# FPGA_OV7670.net
KiCad netlist of a schematic drawn in Altium Designer
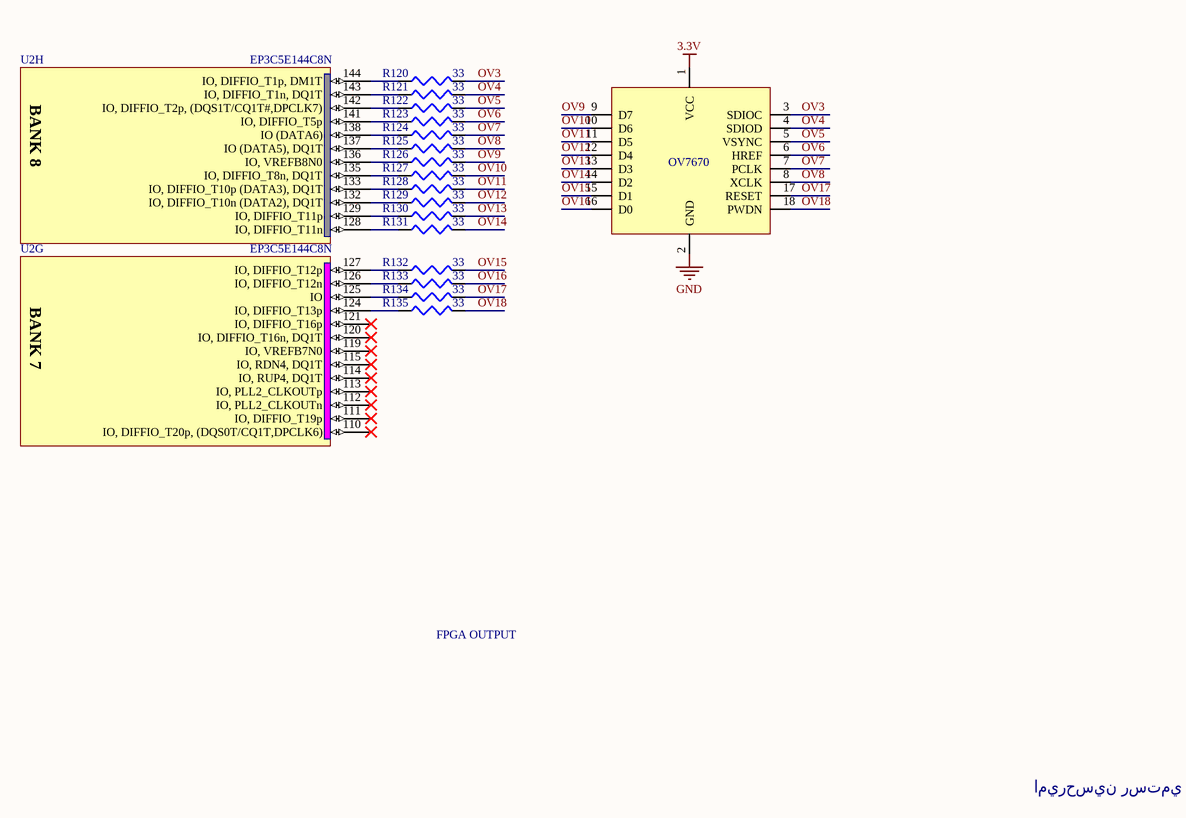
[diagram p0: FPGA_OV7670.SchDoc]

(export (version "E")
  (design (tool "Eeschema 10.0.6"))
  (components
    (comp (ref "*") (value "Component_1") (libsource (lib "OV7670") (part "Component_1")))
    (comp (ref "R120")
      (value "33")
      (footprint "J1-0603")
      (description "Resistor")
      (fields (field (name "PUBLISHER") "Altium Limited"))
      (libsource (lib "Miscellaneous Devices") (part "Res3"))
    )
    (comp (ref "R121")
      (value "33")
      (footprint "J1-0603")
      (description "Resistor")
      (fields (field (name "PUBLISHER") "Altium Limited"))
      (libsource (lib "Miscellaneous Devices") (part "Res3"))
    )
    (comp (ref "R122")
      (value "33")
      (footprint "J1-0603")
      (description "Resistor")
      (fields (field (name "PUBLISHER") "Altium Limited"))
      (libsource (lib "Miscellaneous Devices") (part "Res3"))
    )
    (comp (ref "R123")
      (value "33")
      (footprint "J1-0603")
      (description "Resistor")
      (fields (field (name "PUBLISHER") "Altium Limited"))
      (libsource (lib "Miscellaneous Devices") (part "Res3"))
    )
    (comp (ref "R124")
      (value "33")
      (footprint "J1-0603")
      (description "Resistor")
      (fields (field (name "PUBLISHER") "Altium Limited"))
      (libsource (lib "Miscellaneous Devices") (part "Res3"))
    )
    (comp (ref "R125")
      (value "33")
      (footprint "J1-0603")
      (description "Resistor")
      (fields (field (name "PUBLISHER") "Altium Limited"))
      (libsource (lib "Miscellaneous Devices") (part "Res3"))
    )
    (comp (ref "R126")
      (value "33")
      (footprint "J1-0603")
      (description "Resistor")
      (fields (field (name "PUBLISHER") "Altium Limited"))
      (libsource (lib "Miscellaneous Devices") (part "Res3"))
    )
    (comp (ref "R127")
      (value "33")
      (footprint "J1-0603")
      (description "Resistor")
      (fields (field (name "PUBLISHER") "Altium Limited"))
      (libsource (lib "Miscellaneous Devices") (part "Res3"))
    )
    (comp (ref "R128")
      (value "33")
      (footprint "J1-0603")
      (description "Resistor")
      (fields (field (name "PUBLISHER") "Altium Limited"))
      (libsource (lib "Miscellaneous Devices") (part "Res3"))
    )
    (comp (ref "R129")
      (value "33")
      (footprint "J1-0603")
      (description "Resistor")
      (fields (field (name "PUBLISHER") "Altium Limited"))
      (libsource (lib "Miscellaneous Devices") (part "Res3"))
    )
    (comp (ref "R130")
      (value "33")
      (footprint "J1-0603")
      (description "Resistor")
      (fields (field (name "PUBLISHER") "Altium Limited"))
      (libsource (lib "Miscellaneous Devices") (part "Res3"))
    )
    (comp (ref "R131")
      (value "33")
      (footprint "J1-0603")
      (description "Resistor")
      (fields (field (name "PUBLISHER") "Altium Limited"))
      (libsource (lib "Miscellaneous Devices") (part "Res3"))
    )
    (comp (ref "R132")
      (value "33")
      (footprint "J1-0603")
      (description "Resistor")
      (fields (field (name "PUBLISHER") "Altium Limited"))
      (libsource (lib "Miscellaneous Devices") (part "Res3"))
    )
    (comp (ref "R133")
      (value "33")
      (footprint "J1-0603")
      (description "Resistor")
      (fields (field (name "PUBLISHER") "Altium Limited"))
      (libsource (lib "Miscellaneous Devices") (part "Res3"))
    )
    (comp (ref "R134")
      (value "33")
      (footprint "J1-0603")
      (description "Resistor")
      (fields (field (name "PUBLISHER") "Altium Limited"))
      (libsource (lib "Miscellaneous Devices") (part "Res3"))
    )
    (comp (ref "R135")
      (value "33")
      (footprint "J1-0603")
      (description "Resistor")
      (fields (field (name "PUBLISHER") "Altium Limited"))
      (libsource (lib "Miscellaneous Devices") (part "Res3"))
    )
    (comp (ref "U2")
      (value "EP3C5E144C8N")
      (footprint "EQFP144_N")
      (fields (field (name "PUBLISHER") "Altium Limited"))
      (libsource (lib "Altera Cyclone III") (part "EP3C5E144C8N"))
    )
  )
  (nets
    (net (code "1") (name "/OV3") (class "Default")
      (node (ref "*") (pin "3") (pinfunction "SDIOC_3") (pintype "passive"))
      (node (ref "R120") (pin "2") (pinfunction "2_2") (pintype "passive"))
    )
    (net (code "2") (name "/OV4") (class "Default")
      (node (ref "*") (pin "4") (pinfunction "SDIOD_4") (pintype "passive"))
      (node (ref "R121") (pin "2") (pinfunction "2_2") (pintype "passive"))
    )
    (net (code "3") (name "/OV5") (class "Default")
      (node (ref "*") (pin "5") (pinfunction "VSYNC_5") (pintype "passive"))
      (node (ref "R122") (pin "2") (pinfunction "2_2") (pintype "passive"))
    )
    (net (code "4") (name "/OV6") (class "Default")
      (node (ref "*") (pin "6") (pinfunction "HREF_6") (pintype "passive"))
      (node (ref "R123") (pin "2") (pinfunction "2_2") (pintype "passive"))
    )
    (net (code "5") (name "/OV7") (class "Default")
      (node (ref "*") (pin "7") (pinfunction "PCLK_7") (pintype "passive"))
      (node (ref "R124") (pin "2") (pinfunction "2_2") (pintype "passive"))
    )
    (net (code "6") (name "/OV8") (class "Default")
      (node (ref "*") (pin "8") (pinfunction "XCLK_8") (pintype "passive"))
      (node (ref "R125") (pin "2") (pinfunction "2_2") (pintype "passive"))
    )
    (net (code "7") (name "/OV9") (class "Default")
      (node (ref "*") (pin "9") (pinfunction "D7_9") (pintype "passive"))
      (node (ref "R126") (pin "2") (pinfunction "2_2") (pintype "passive"))
    )
    (net (code "8") (name "/OV10") (class "Default")
      (node (ref "*") (pin "10") (pinfunction "D6_10") (pintype "passive"))
      (node (ref "R127") (pin "2") (pinfunction "2_2") (pintype "passive"))
    )
    (net (code "9") (name "/OV11") (class "Default")
      (node (ref "*") (pin "11") (pinfunction "D5_11") (pintype "passive"))
      (node (ref "R128") (pin "2") (pinfunction "2_2") (pintype "passive"))
    )
    (net (code "10") (name "/OV12") (class "Default")
      (node (ref "*") (pin "12") (pinfunction "D4_12") (pintype "passive"))
      (node (ref "R129") (pin "2") (pinfunction "2_2") (pintype "passive"))
    )
    (net (code "11") (name "/OV13") (class "Default")
      (node (ref "*") (pin "13") (pinfunction "D3_13") (pintype "passive"))
      (node (ref "R130") (pin "2") (pinfunction "2_2") (pintype "passive"))
    )
    (net (code "12") (name "/OV14") (class "Default")
      (node (ref "*") (pin "14") (pinfunction "D2_14") (pintype "passive"))
      (node (ref "R131") (pin "2") (pinfunction "2_2") (pintype "passive"))
    )
    (net (code "13") (name "/OV15") (class "Default")
      (node (ref "*") (pin "15") (pinfunction "D1_15") (pintype "passive"))
      (node (ref "R132") (pin "2") (pinfunction "2_2") (pintype "passive"))
    )
    (net (code "14") (name "/OV16") (class "Default")
      (node (ref "*") (pin "16") (pinfunction "D0_16") (pintype "passive"))
      (node (ref "R133") (pin "2") (pinfunction "2_2") (pintype "passive"))
    )
    (net (code "15") (name "/OV17") (class "Default")
      (node (ref "*") (pin "17") (pinfunction "RESET_17") (pintype "passive"))
      (node (ref "R134") (pin "2") (pinfunction "2_2") (pintype "passive"))
    )
    (net (code "16") (name "/OV18") (class "Default")
      (node (ref "*") (pin "18") (pinfunction "PWDN_18") (pintype "passive"))
      (node (ref "R135") (pin "2") (pinfunction "2_2") (pintype "passive"))
    )
    (net (code "17") (name "3.3V") (class "Default")
      (node (ref "*") (pin "1") (pinfunction "VCC_1") (pintype "passive"))
    )
    (net (code "18") (name "GND") (class "Default")
      (node (ref "*") (pin "2") (pinfunction "GND_2") (pintype "passive"))
    )
    (net (code "19") (name "Net-(U2G-IO)") (class "Default")
      (node (ref "R134") (pin "1") (pinfunction "1_1") (pintype "passive"))
      (node (ref "U2") (pin "125") (pinfunction "IO_125") (pintype "bidirectional"))
    )
    (net (code "20") (name "Net-(U2G-IO,_DIFFIO_T12n)") (class "Default")
      (node (ref "R133") (pin "1") (pinfunction "1_1") (pintype "passive"))
      (node (ref "U2") (pin "126") (pinfunction "IO,_DIFFIO_T12n_126") (pintype "bidirectional"))
    )
    (net (code "21") (name "Net-(U2G-IO,_DIFFIO_T12p)") (class "Default")
      (node (ref "R132") (pin "1") (pinfunction "1_1") (pintype "passive"))
      (node (ref "U2") (pin "127") (pinfunction "IO,_DIFFIO_T12p_127") (pintype "bidirectional"))
    )
    (net (code "22") (name "Net-(U2G-IO,_DIFFIO_T13p)") (class "Default")
      (node (ref "R135") (pin "1") (pinfunction "1_1") (pintype "passive"))
      (node (ref "U2") (pin "124") (pinfunction "IO,_DIFFIO_T13p_124") (pintype "bidirectional"))
    )
    (net (code "23") (name "Net-(U2H-IO,_DIFFIO_T1n,_DQ1T)") (class "Default")
      (node (ref "R121") (pin "1") (pinfunction "1_1") (pintype "passive"))
      (node (ref "U2") (pin "143") (pinfunction "IO,_DIFFIO_T1n,_DQ1T_143") (pintype "bidirectional"))
    )
    (net (code "24") (name "Net-(U2H-IO,_DIFFIO_T1p,_DM1T)") (class "Default")
      (node (ref "R120") (pin "1") (pinfunction "1_1") (pintype "passive"))
      (node (ref "U2") (pin "144") (pinfunction "IO,_DIFFIO_T1p,_DM1T_144") (pintype "bidirectional"))
    )
    (net (code "25") (name "Net-(U2H-IO,_DIFFIO_T2p,_(DQS1T{slash}CQ1T#,DPCLK7))") (class "Default")
      (node (ref "R122") (pin "1") (pinfunction "1_1") (pintype "passive"))
      (node (ref "U2") (pin "142") (pinfunction "IO,_DIFFIO_T2p,_(DQS1T/CQ1T#,DPCLK7)_142") (pintype "bidirectional"))
    )
    (net (code "26") (name "Net-(U2H-IO,_DIFFIO_T5p)") (class "Default")
      (node (ref "R123") (pin "1") (pinfunction "1_1") (pintype "passive"))
      (node (ref "U2") (pin "141") (pinfunction "IO,_DIFFIO_T5p_141") (pintype "bidirectional"))
    )
    (net (code "27") (name "Net-(U2H-IO,_DIFFIO_T8n,_DQ1T)") (class "Default")
      (node (ref "R127") (pin "1") (pinfunction "1_1") (pintype "passive"))
      (node (ref "U2") (pin "135") (pinfunction "IO,_DIFFIO_T8n,_DQ1T_135") (pintype "bidirectional"))
    )
    (net (code "28") (name "Net-(U2H-IO,_DIFFIO_T10n_(DATA2),_DQ1T)") (class "Default")
      (node (ref "R129") (pin "1") (pinfunction "1_1") (pintype "passive"))
      (node (ref "U2") (pin "132") (pinfunction "IO,_DIFFIO_T10n_(DATA2),_DQ1T_132") (pintype "bidirectional"))
    )
    (net (code "29") (name "Net-(U2H-IO,_DIFFIO_T10p_(DATA3),_DQ1T)") (class "Default")
      (node (ref "R128") (pin "1") (pinfunction "1_1") (pintype "passive"))
      (node (ref "U2") (pin "133") (pinfunction "IO,_DIFFIO_T10p_(DATA3),_DQ1T_133") (pintype "bidirectional"))
    )
    (net (code "30") (name "Net-(U2H-IO,_DIFFIO_T11n)") (class "Default")
      (node (ref "R131") (pin "1") (pinfunction "1_1") (pintype "passive"))
      (node (ref "U2") (pin "128") (pinfunction "IO,_DIFFIO_T11n_128") (pintype "bidirectional"))
    )
    (net (code "31") (name "Net-(U2H-IO,_DIFFIO_T11p)") (class "Default")
      (node (ref "R130") (pin "1") (pinfunction "1_1") (pintype "passive"))
      (node (ref "U2") (pin "129") (pinfunction "IO,_DIFFIO_T11p_129") (pintype "bidirectional"))
    )
    (net (code "32") (name "Net-(U2H-IO,_VREFB8N0)") (class "Default")
      (node (ref "R126") (pin "1") (pinfunction "1_1") (pintype "passive"))
      (node (ref "U2") (pin "136") (pinfunction "IO,_VREFB8N0_136") (pintype "bidirectional"))
    )
    (net (code "33") (name "Net-(U2H-IO_(DATA5),_DQ1T)") (class "Default")
      (node (ref "R125") (pin "1") (pinfunction "1_1") (pintype "passive"))
      (node (ref "U2") (pin "137") (pinfunction "IO_(DATA5),_DQ1T_137") (pintype "bidirectional"))
    )
    (net (code "34") (name "Net-(U2H-IO_(DATA6))") (class "Default")
      (node (ref "R124") (pin "1") (pinfunction "1_1") (pintype "passive"))
      (node (ref "U2") (pin "138") (pinfunction "IO_(DATA6)_138") (pintype "bidirectional"))
    )
    (net (code "35") (name "unconnected-(U2G-IO,_DIFFIO_T16n,_DQ1T-Pad120)") (class "Default")
      (node (ref "U2") (pin "120") (pinfunction "IO,_DIFFIO_T16n,_DQ1T_120") (pintype "bidirectional+no_connect"))
    )
    (net (code "36") (name "unconnected-(U2G-IO,_DIFFIO_T16p-Pad121)") (class "Default")
      (node (ref "U2") (pin "121") (pinfunction "IO,_DIFFIO_T16p_121") (pintype "bidirectional+no_connect"))
    )
    (net (code "37") (name "unconnected-(U2G-IO,_DIFFIO_T19p-Pad111)") (class "Default")
      (node (ref "U2") (pin "111") (pinfunction "IO,_DIFFIO_T19p_111") (pintype "bidirectional+no_connect"))
    )
    (net (code "38") (name "unconnected-(U2G-IO,_DIFFIO_T20p,_(DQS0T{slash}CQ1T,DPCLK6)-Pad110)") (class "Default")
      (node (ref "U2") (pin "110") (pinfunction "IO,_DIFFIO_T20p,_(DQS0T/CQ1T,DPCLK6)_110") (pintype "bidirectional+no_connect"))
    )
    (net (code "39") (name "unconnected-(U2G-IO,_PLL2_CLKOUTn-Pad112)") (class "Default")
      (node (ref "U2") (pin "112") (pinfunction "IO,_PLL2_CLKOUTn_112") (pintype "bidirectional+no_connect"))
    )
    (net (code "40") (name "unconnected-(U2G-IO,_PLL2_CLKOUTp-Pad113)") (class "Default")
      (node (ref "U2") (pin "113") (pinfunction "IO,_PLL2_CLKOUTp_113") (pintype "bidirectional+no_connect"))
    )
    (net (code "41") (name "unconnected-(U2G-IO,_RDN4,_DQ1T-Pad115)") (class "Default")
      (node (ref "U2") (pin "115") (pinfunction "IO,_RDN4,_DQ1T_115") (pintype "bidirectional+no_connect"))
    )
    (net (code "42") (name "unconnected-(U2G-IO,_RUP4,_DQ1T-Pad114)") (class "Default")
      (node (ref "U2") (pin "114") (pinfunction "IO,_RUP4,_DQ1T_114") (pintype "bidirectional+no_connect"))
    )
    (net (code "43") (name "unconnected-(U2G-IO,_VREFB7N0-Pad119)") (class "Default")
      (node (ref "U2") (pin "119") (pinfunction "IO,_VREFB7N0_119") (pintype "bidirectional+no_connect"))
    )
  )
)
